# CW340_HEATSINK_FAN.net
KiCad netlist of a schematic drawn in Altium Designer
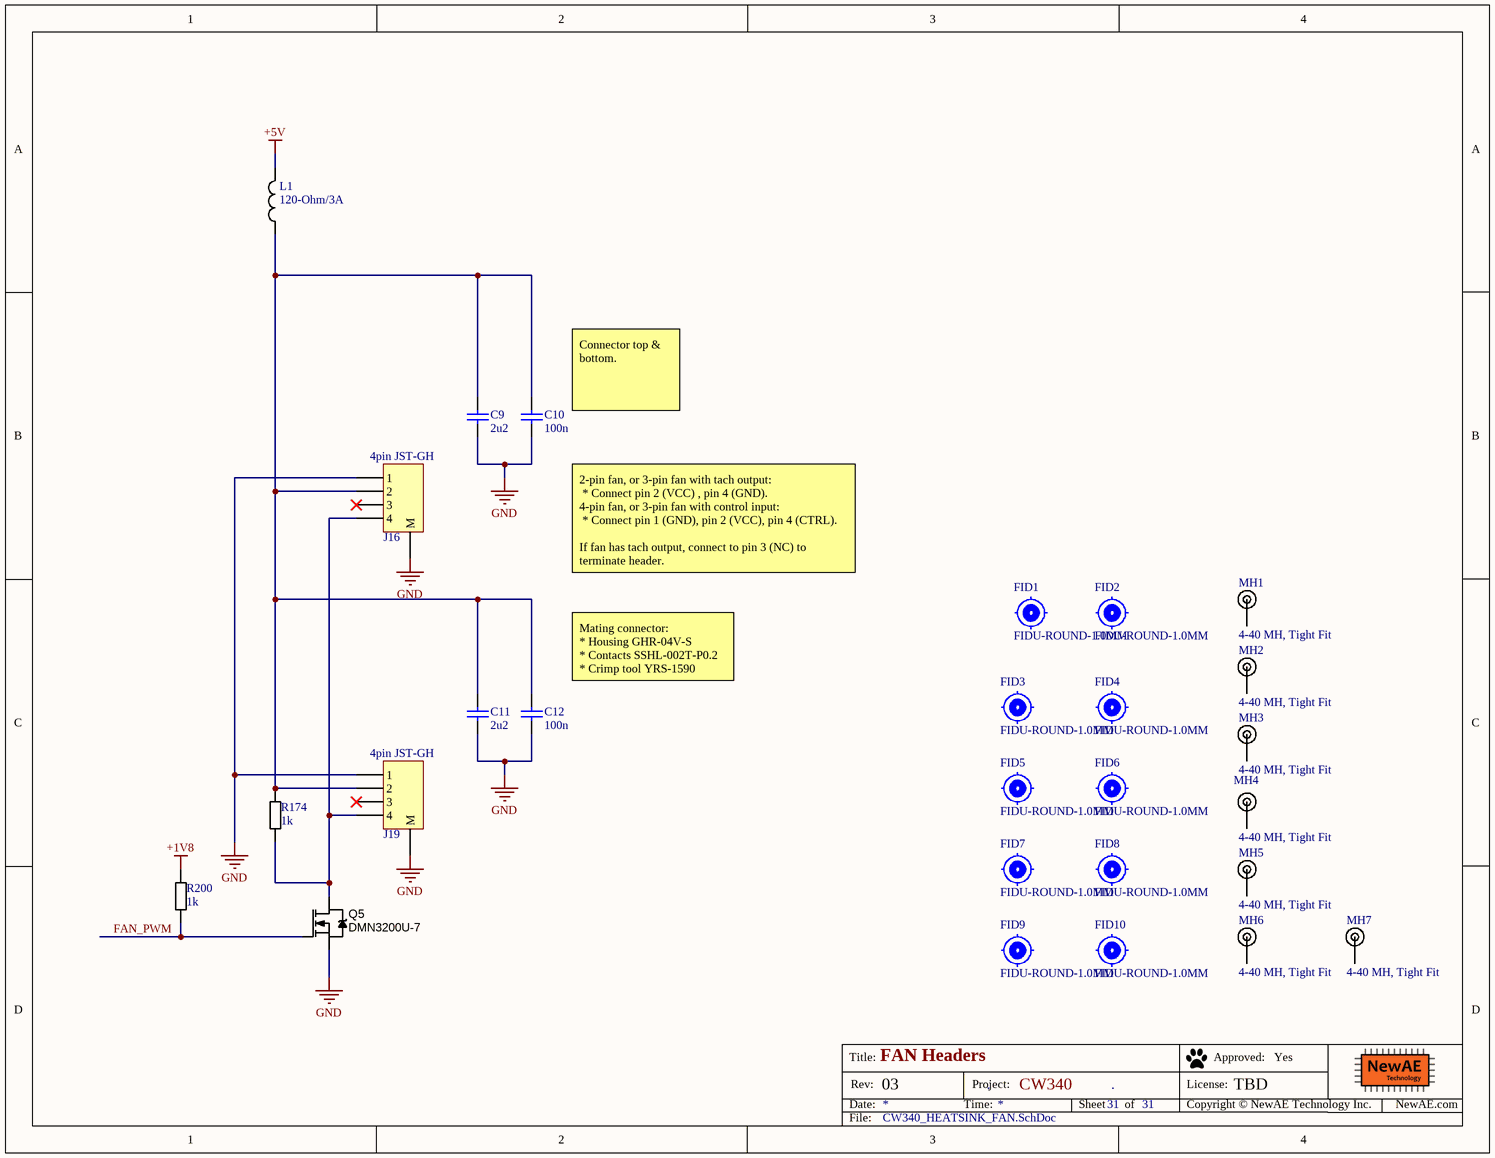
[diagram p0: CW340_HEATSINK_FAN.SchDoc]

(export (version "E")
  (design (tool "Eeschema 10.0.6"))
  (components
    (comp (ref "C9")
      (value "2u2")
      (footprint "CAPC0603_M")
      (description "2u2, 0603")
      (fields (field (name "PART NUMBER") "CCHIP-2u2-0603"))
      (libsource (lib "NewAE_AltiumLib") (part "CAP"))
    )
    (comp (ref "C10")
      (value "100n")
      (footprint "CAPC0402_M")
      (description "100n, 0402")
      (fields (field (name "PART NUMBER") "CCHIP-100n-0402"))
      (libsource (lib "NewAE_AltiumLib") (part "CAP"))
    )
    (comp (ref "C11")
      (value "2u2")
      (footprint "CAPC0603_M")
      (description "2u2, 0603")
      (fields (field (name "PART NUMBER") "CCHIP-2u2-0603"))
      (libsource (lib "NewAE_AltiumLib") (part "CAP"))
    )
    (comp (ref "C12")
      (value "100n")
      (footprint "CAPC0402_M")
      (description "100n, 0402")
      (fields (field (name "PART NUMBER") "CCHIP-100n-0402"))
      (libsource (lib "NewAE_AltiumLib") (part "CAP"))
    )
    (comp (ref "FID1")
      (value "FIDU-ROUND-1.0MM")
      (footprint "FIDU-ROUND-1.0mm")
      (description "ROUND FIDUCIAL")
      (libsource (lib "NewAE_AltiumLib") (part "FIDU-ROUND-1.0MM"))
    )
    (comp (ref "FID2")
      (value "FIDU-ROUND-1.0MM")
      (footprint "FIDU-ROUND-1.0mm")
      (description "ROUND FIDUCIAL")
      (libsource (lib "NewAE_AltiumLib") (part "FIDU-ROUND-1.0MM"))
    )
    (comp (ref "FID3")
      (value "FIDU-ROUND-1.0MM")
      (footprint "FIDU-ROUND-1.0mm")
      (description "ROUND FIDUCIAL")
      (libsource (lib "NewAE_AltiumLib") (part "FIDU-ROUND-1.0MM"))
    )
    (comp (ref "FID4")
      (value "FIDU-ROUND-1.0MM")
      (footprint "FIDU-ROUND-1.0mm")
      (description "ROUND FIDUCIAL")
      (libsource (lib "NewAE_AltiumLib") (part "FIDU-ROUND-1.0MM"))
    )
    (comp (ref "FID5")
      (value "FIDU-ROUND-1.0MM")
      (footprint "FIDU-ROUND-1.0mm")
      (description "ROUND FIDUCIAL")
      (libsource (lib "NewAE_AltiumLib") (part "FIDU-ROUND-1.0MM"))
    )
    (comp (ref "FID6")
      (value "FIDU-ROUND-1.0MM")
      (footprint "FIDU-ROUND-1.0mm")
      (description "ROUND FIDUCIAL")
      (libsource (lib "NewAE_AltiumLib") (part "FIDU-ROUND-1.0MM"))
    )
    (comp (ref "FID7")
      (value "FIDU-ROUND-1.0MM")
      (footprint "FIDU-ROUND-1.0mm")
      (description "ROUND FIDUCIAL")
      (libsource (lib "NewAE_AltiumLib") (part "FIDU-ROUND-1.0MM"))
    )
    (comp (ref "FID8")
      (value "FIDU-ROUND-1.0MM")
      (footprint "FIDU-ROUND-1.0mm")
      (description "ROUND FIDUCIAL")
      (libsource (lib "NewAE_AltiumLib") (part "FIDU-ROUND-1.0MM"))
    )
    (comp (ref "FID9")
      (value "FIDU-ROUND-1.0MM")
      (footprint "FIDU-ROUND-1.0mm")
      (description "ROUND FIDUCIAL")
      (libsource (lib "NewAE_AltiumLib") (part "FIDU-ROUND-1.0MM"))
    )
    (comp (ref "FID10")
      (value "FIDU-ROUND-1.0MM")
      (footprint "FIDU-ROUND-1.0mm")
      (description "ROUND FIDUCIAL")
      (libsource (lib "NewAE_AltiumLib") (part "FIDU-ROUND-1.0MM"))
    )
    (comp (ref "J16")
      (value "4pin JST-GH")
      (footprint "BM04B-GHS-TBT")
      (description "CONN HEADER SMD 4POS 1.25MM")
      (fields (field (name "PART NUMBER") "BM04B-GHS-TBT"))
      (libsource (lib "NewAE_AltiumLib") (part "BM04B-GHS-TBT"))
    )
    (comp (ref "J19")
      (value "4pin JST-GH")
      (footprint "BM04B-GHS-TBT")
      (description "CONN HEADER SMD 4POS 1.25MM")
      (fields (field (name "PART NUMBER") "BM04B-GHS-TBT"))
      (libsource (lib "NewAE_AltiumLib") (part "BM04B-GHS-TBT"))
    )
    (comp (ref "L1")
      (value "120-Ohm/3A")
      (footprint "IND_0603")
      (description "120 Ohm @ 100 MHz, 3A rated FB")
      (fields (field (name "PART NUMBER") "FBCHIP-120R-0603"))
      (libsource (lib "NewAE_AltiumLib") (part "IND"))
    )
    (comp (ref "MH1")
      (value "4-40 MH, Tight Fit")
      (footprint "MOUNT_#4_TIGHT")
      (description "Machine screw 4-40 Mounting Hole")
      (fields (field (name "PART NUMBER") "MOUNT_#4_TIGHT"))
      (libsource (lib "NewAE_AltiumLib") (part "Mounting_Hole"))
    )
    (comp (ref "MH2")
      (value "4-40 MH, Tight Fit")
      (footprint "MOUNT_#4_TIGHT")
      (description "Machine screw 4-40 Mounting Hole")
      (fields (field (name "PART NUMBER") "MOUNT_#4_TIGHT"))
      (libsource (lib "NewAE_AltiumLib") (part "Mounting_Hole"))
    )
    (comp (ref "MH3")
      (value "4-40 MH, Tight Fit")
      (footprint "MOUNT_#4_TIGHT")
      (description "Machine screw 4-40 Mounting Hole")
      (fields (field (name "PART NUMBER") "MOUNT_#4_TIGHT"))
      (libsource (lib "NewAE_AltiumLib") (part "Mounting_Hole"))
    )
    (comp (ref "MH4")
      (value "4-40 MH, Tight Fit")
      (footprint "MOUNT_#4_TIGHT")
      (description "Machine screw 4-40 Mounting Hole")
      (fields (field (name "PART NUMBER") "MOUNT_#4_TIGHT"))
      (libsource (lib "NewAE_AltiumLib") (part "Mounting_Hole"))
    )
    (comp (ref "MH5")
      (value "4-40 MH, Tight Fit")
      (footprint "MOUNT_#4_TIGHT")
      (description "Machine screw 4-40 Mounting Hole")
      (fields (field (name "PART NUMBER") "MOUNT_#4_TIGHT"))
      (libsource (lib "NewAE_AltiumLib") (part "Mounting_Hole"))
    )
    (comp (ref "MH6")
      (value "4-40 MH, Tight Fit")
      (footprint "MOUNT_#4_TIGHT")
      (description "Machine screw 4-40 Mounting Hole")
      (fields (field (name "PART NUMBER") "MOUNT_#4_TIGHT"))
      (libsource (lib "NewAE_AltiumLib") (part "Mounting_Hole"))
    )
    (comp (ref "MH7")
      (value "4-40 MH, Tight Fit")
      (footprint "MOUNT_#4_TIGHT")
      (description "Machine screw 4-40 Mounting Hole")
      (fields (field (name "PART NUMBER") "MOUNT_#4_TIGHT"))
      (libsource (lib "NewAE_AltiumLib") (part "Mounting_Hole"))
    )
    (comp (ref "Q5")
      (value "DMN3200U-7")
      (footprint "SOT95P245X110-3M")
      (description "MOSFET N-CH 30V 2.2A SOT23-3")
      (libsource (lib "NewAE_AltiumLib") (part "MOSFET_N_GSD"))
    )
    (comp (ref "R174")
      (value "1k")
      (footprint "RESC1005X40N")
      (description "1k res, 0402, 1%, 1/16W")
      (fields (field (name "PART NUMBER") "RCHIP-1K-0402") (field (name "TOLERANCE") "1%"))
      (libsource (lib "NewAE_AltiumLib") (part "RES-EU"))
    )
    (comp (ref "R200")
      (value "1k")
      (footprint "RESC1005X40N")
      (description "1k res, 0402, 1%, 1/16W")
      (fields (field (name "PART NUMBER") "RCHIP-1K-0402") (field (name "TOLERANCE") "1%"))
      (libsource (lib "NewAE_AltiumLib") (part "RES-EU"))
    )
  )
  (nets
    (net (code "1") (name "+1V8") (class "Default")
      (node (ref "R200") (pin "1") (pinfunction "1_1") (pintype "passive"))
    )
    (net (code "2") (name "+5V") (class "Default")
      (node (ref "L1") (pin "2") (pinfunction "2_2") (pintype "passive"))
    )
    (net (code "3") (name "/FAN_PWM") (class "Default")
      (node (ref "Q5") (pin "1") (pinfunction "G_1") (pintype "passive"))
      (node (ref "R200") (pin "2") (pinfunction "2_2") (pintype "passive"))
    )
    (net (code "4") (name "GND") (class "Default")
      (node (ref "C10") (pin "2") (pinfunction "2_2") (pintype "passive"))
      (node (ref "C11") (pin "2") (pinfunction "2_2") (pintype "passive"))
      (node (ref "C12") (pin "2") (pinfunction "2_2") (pintype "passive"))
      (node (ref "C9") (pin "2") (pinfunction "2_2") (pintype "passive"))
      (node (ref "J16") (pin "1") (pinfunction "1_1") (pintype "passive"))
      (node (ref "J16") (pin "M") (pinfunction "M_M") (pintype "passive"))
      (node (ref "J19") (pin "1") (pinfunction "1_1") (pintype "passive"))
      (node (ref "J19") (pin "M") (pinfunction "M_M") (pintype "passive"))
      (node (ref "Q5") (pin "2") (pinfunction "S_2") (pintype "passive"))
    )
    (net (code "5") (name "Net-(C10-Pad1)") (class "Default")
      (node (ref "C10") (pin "1") (pinfunction "1_1") (pintype "passive"))
      (node (ref "C11") (pin "1") (pinfunction "1_1") (pintype "passive"))
      (node (ref "C12") (pin "1") (pinfunction "1_1") (pintype "passive"))
      (node (ref "C9") (pin "1") (pinfunction "1_1") (pintype "passive"))
      (node (ref "J16") (pin "2") (pinfunction "2_2") (pintype "passive"))
      (node (ref "J19") (pin "2") (pinfunction "2_2") (pintype "passive"))
      (node (ref "L1") (pin "1") (pinfunction "1_1") (pintype "passive"))
      (node (ref "R174") (pin "1") (pinfunction "1_1") (pintype "passive"))
    )
    (net (code "6") (name "Net-(Q5-D)") (class "Default")
      (node (ref "J16") (pin "4") (pinfunction "4_4") (pintype "passive"))
      (node (ref "J19") (pin "4") (pinfunction "4_4") (pintype "passive"))
      (node (ref "Q5") (pin "3") (pinfunction "D_3") (pintype "passive"))
      (node (ref "R174") (pin "2") (pinfunction "2_2") (pintype "passive"))
    )
    (net (code "7") (name "unconnected-(J16-Pad3)") (class "Default")
      (node (ref "J16") (pin "3") (pinfunction "3_3") (pintype "passive+no_connect"))
    )
    (net (code "8") (name "unconnected-(J19-Pad3)") (class "Default")
      (node (ref "J19") (pin "3") (pinfunction "3_3") (pintype "passive+no_connect"))
    )
    (net (code "9") (name "unconnected-(MH1-Pad1)") (class "Default")
      (node (ref "MH1") (pin "1") (pinfunction "1_1") (pintype "passive"))
    )
    (net (code "10") (name "unconnected-(MH2-Pad1)") (class "Default")
      (node (ref "MH2") (pin "1") (pinfunction "1_1") (pintype "passive"))
    )
    (net (code "11") (name "unconnected-(MH3-Pad1)") (class "Default")
      (node (ref "MH3") (pin "1") (pinfunction "1_1") (pintype "passive"))
    )
    (net (code "12") (name "unconnected-(MH4-Pad1)") (class "Default")
      (node (ref "MH4") (pin "1") (pinfunction "1_1") (pintype "passive"))
    )
    (net (code "13") (name "unconnected-(MH5-Pad1)") (class "Default")
      (node (ref "MH5") (pin "1") (pinfunction "1_1") (pintype "passive"))
    )
    (net (code "14") (name "unconnected-(MH6-Pad1)") (class "Default")
      (node (ref "MH6") (pin "1") (pinfunction "1_1") (pintype "passive"))
    )
    (net (code "15") (name "unconnected-(MH7-Pad1)") (class "Default")
      (node (ref "MH7") (pin "1") (pinfunction "1_1") (pintype "passive"))
    )
  )
)
